# other.net
KiCad netlist of a schematic drawn in Altium Designer
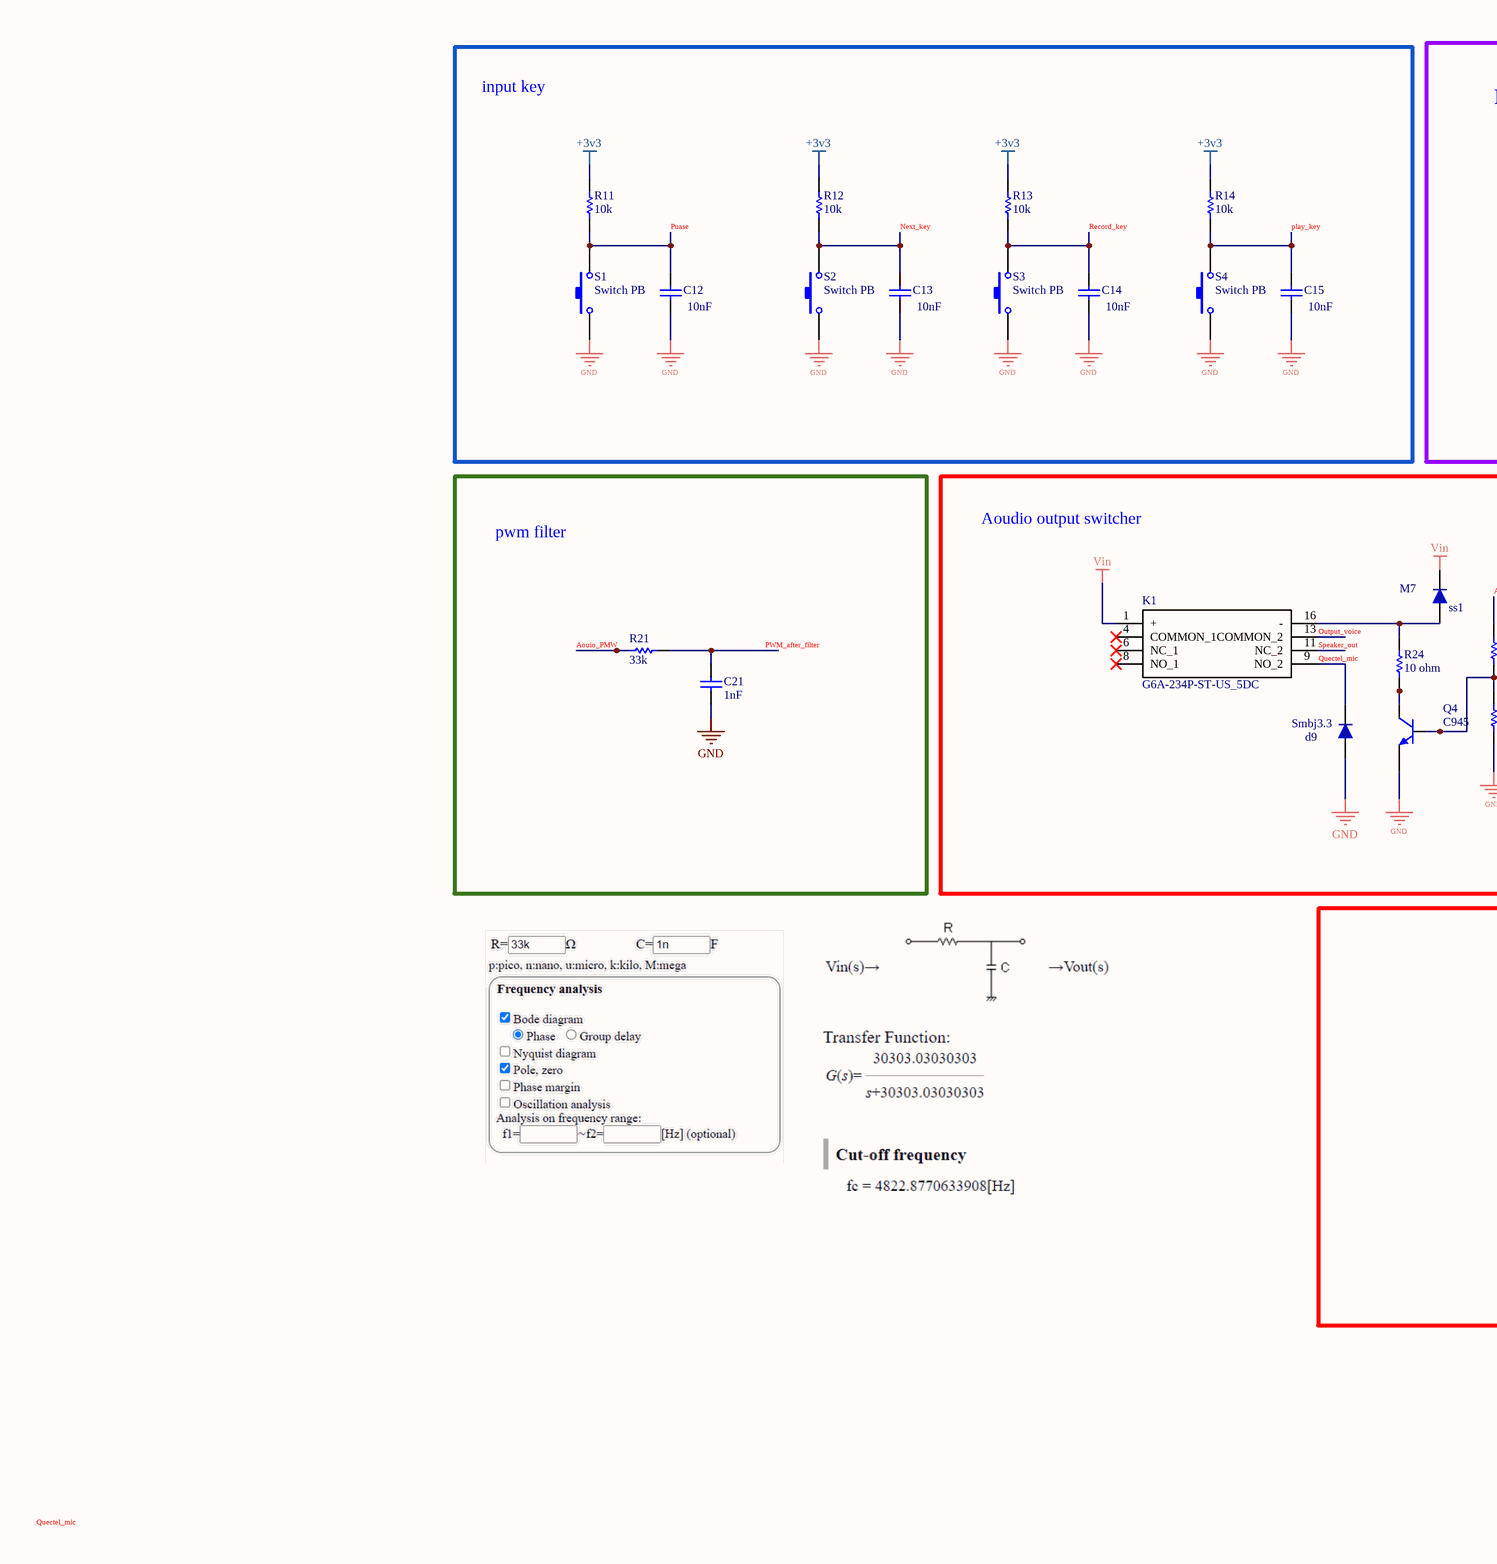
[diagram p0: other.SchDoc, left]
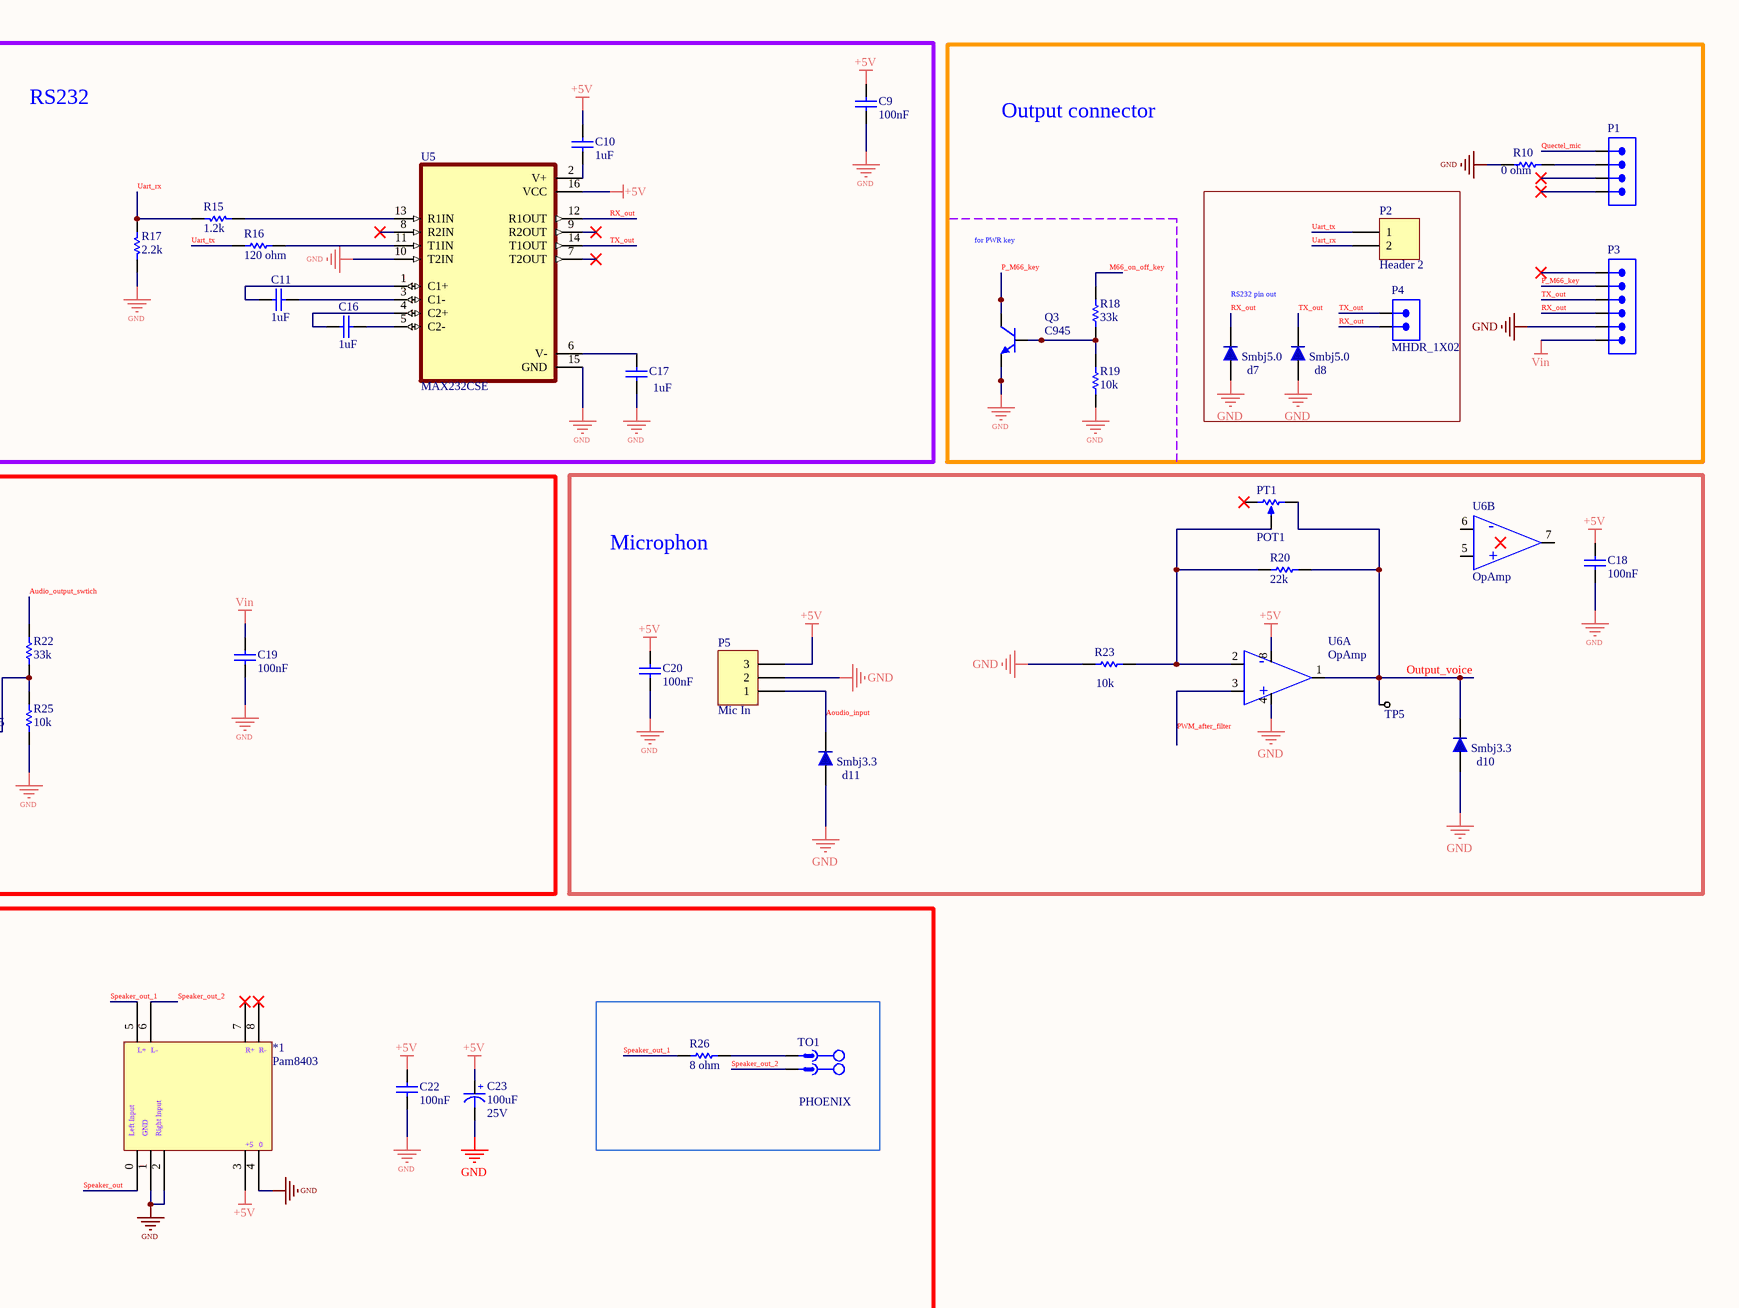
[diagram p1: other.SchDoc, right]

(export (version "E")
  (design (tool "Eeschema 10.0.6"))
  (components
    (comp (ref "*1") (value "Pam8403") (footprint "PAM8403") (libsource (lib "PAM8403") (part "Pam8403")))
    (comp (ref "C9")
      (value "100nF")
      (footprint "CAP805")
      (description "Capacitor")
      (fields (field (name "PUBLISHER") "Altium Limited"))
      (libsource (lib "componnect") (part "Cap"))
    )
    (comp (ref "C10")
      (value "1uF")
      (footprint "CAP805")
      (description "Capacitor")
      (fields (field (name "PUBLISHER") "Altium Limited"))
      (libsource (lib "componnect") (part "Cap"))
    )
    (comp (ref "C11")
      (value "1uF")
      (footprint "CAP805")
      (description "Capacitor")
      (fields (field (name "PUBLISHER") "Altium Limited"))
      (libsource (lib "componnect") (part "Cap"))
    )
    (comp (ref "C12")
      (value "10nF")
      (footprint "CAP805")
      (description "Capacitor")
      (fields (field (name "PUBLISHER") "Altium Limited"))
      (libsource (lib "componnect") (part "Cap"))
    )
    (comp (ref "C13")
      (value "10nF")
      (footprint "CAP805")
      (description "Capacitor")
      (fields (field (name "PUBLISHER") "Altium Limited"))
      (libsource (lib "componnect") (part "Cap"))
    )
    (comp (ref "C14")
      (value "10nF")
      (footprint "CAP805")
      (description "Capacitor")
      (fields (field (name "PUBLISHER") "Altium Limited"))
      (libsource (lib "componnect") (part "Cap"))
    )
    (comp (ref "C15")
      (value "10nF")
      (footprint "CAP805")
      (description "Capacitor")
      (fields (field (name "PUBLISHER") "Altium Limited"))
      (libsource (lib "componnect") (part "Cap"))
    )
    (comp (ref "C16")
      (value "1uF")
      (footprint "CAP805")
      (description "Capacitor")
      (fields (field (name "PUBLISHER") "Altium Limited"))
      (libsource (lib "componnect") (part "Cap"))
    )
    (comp (ref "C17")
      (value "1uF")
      (footprint "CAP805")
      (description "Capacitor")
      (fields (field (name "PUBLISHER") "Altium Limited"))
      (libsource (lib "componnect") (part "Cap"))
    )
    (comp (ref "C18")
      (value "100nF")
      (footprint "CAP805")
      (description "Capacitor")
      (fields (field (name "PUBLISHER") "Altium Limited"))
      (libsource (lib "componnect") (part "Cap"))
    )
    (comp (ref "C19")
      (value "100nF")
      (footprint "CAP805")
      (description "Capacitor")
      (fields (field (name "PUBLISHER") "Altium Limited"))
      (libsource (lib "componnect") (part "Cap"))
    )
    (comp (ref "C20")
      (value "100nF")
      (footprint "CAP805")
      (description "Capacitor")
      (fields (field (name "PUBLISHER") "Altium Limited"))
      (libsource (lib "componnect") (part "Cap"))
    )
    (comp (ref "C21")
      (value "1nF")
      (footprint "CAP805")
      (description "Capacitor")
      (fields (field (name "PUBLISHER") "Altium Limited"))
      (libsource (lib "componnect") (part "Cap"))
    )
    (comp (ref "C22")
      (value "100nF")
      (footprint "CAP805")
      (description "Capacitor")
      (fields (field (name "PUBLISHER") "Altium Limited"))
      (libsource (lib "componnect") (part "Cap"))
    )
    (comp (ref "C23")
      (value "100uF")
      (footprint "cap 03")
      (description "Polar Capacitor")
      (fields
        (field (name "VOLTAGE") "25V")
        (field (name "DESIGNER") "Eng. Saeid Jorablo")
        (field (name "PUBLISHER") "SJ Unlimited")
      )
      (libsource (lib "Schematic") (part "CAP_Polar"))
    )
    (comp (ref "d7")
      (value "Smbj5.0")
      (footprint "DIODE SMA (DO-214AC)")
      (fields (field (name "MANUFACTURER") "DC COMPONENTS") (field (name "DESIGNER") "Abbas Basereh"))
      (libsource (lib "componnect") (part "1n4007 SMD M7"))
    )
    (comp (ref "d8")
      (value "Smbj5.0")
      (footprint "DIODE SMA (DO-214AC)")
      (fields (field (name "MANUFACTURER") "DC COMPONENTS") (field (name "DESIGNER") "Abbas Basereh"))
      (libsource (lib "componnect") (part "1n4007 SMD M7"))
    )
    (comp (ref "d9")
      (value "Smbj3.3")
      (footprint "DIODE SMA (DO-214AC)")
      (description "Smbj5.0")
      (fields (field (name "MANUFACTURER") "DC COMPONENTS") (field (name "DESIGNER") "Abbas Basereh"))
      (libsource (lib "componnect") (part "1n4007 SMD M7"))
    )
    (comp (ref "d10")
      (value "Smbj3.3")
      (footprint "DIODE SMA (DO-214AC)")
      (description "Smbj5.0")
      (fields (field (name "MANUFACTURER") "DC COMPONENTS") (field (name "DESIGNER") "Abbas Basereh"))
      (libsource (lib "componnect") (part "1n4007 SMD M7"))
    )
    (comp (ref "d11")
      (value "Smbj3.3")
      (footprint "DIODE SMA (DO-214AC)")
      (description "Smbj5.0")
      (fields (field (name "MANUFACTURER") "DC COMPONENTS") (field (name "DESIGNER") "Abbas Basereh"))
      (libsource (lib "componnect") (part "1n4007 SMD M7"))
    )
    (comp (ref "K1")
      (value "G6A-234P-ST-US_5DC")
      (footprint "G6A234PSTUS5DC")
      (description "Relay or Contactor")
      (fields (field (name "MANUFACTURER_PART_NUMBER") "G6A-234P-ST-US 5DC"))
      (libsource (lib "*") (part "G6A-234P-ST-US_5DC"))
    )
    (comp (ref "P1")
      (value "xh 4pin")
      (footprint "XH 4 PIN-S")
      (libsource (lib "Connector_15 and Sockets") (part "MHDR_1X04"))
    )
    (comp (ref "P2")
      (value "Header 2")
      (footprint "HDR1X2")
      (description "Header, 2-Pin")
      (fields (field (name "PUBLISHER") "Altium Limited"))
      (libsource (lib "Schematic") (part "Header 2"))
    )
    (comp (ref "P3")
      (value "xh 6pin")
      (footprint "XH 6 PIN-S")
      (libsource (lib "Connector_15 and Sockets") (part "MHDR_1X06"))
    )
    (comp (ref "P4")
      (value "MHDR_1X02")
      (footprint "MHDR1X02-254P")
      (description "Male Header 1X02")
      (libsource (lib "Connector_15 and Sockets") (part "MHDR_1X02"))
    )
    (comp (ref "P5")
      (value "Mic In")
      (footprint "HDR1X3")
      (description "Header, 3-Pin")
      (fields (field (name "PUBLISHER") "Altium Limited"))
      (libsource (lib "Schematic") (part "Header 3"))
    )
    (comp (ref "PT1")
      (value "POT1")
      (footprint "POT1")
      (description "Variable Potentiometer standing")
      (fields (field (name "DESIGNER") "Seyed Mohsen Ghasemian"))
      (libsource (lib "usefully_Library") (part "POT1"))
    )
    (comp (ref "Q3")
      (value "C945")
      (footprint "C945")
      (description "NPN Transistor")
      (fields (field (name "DESIGNER") "Saeid Jorablo"))
      (libsource (lib "Schematic") (part "C945 2"))
    )
    (comp (ref "Q4")
      (value "C945")
      (footprint "C945")
      (description "NPN Transistor")
      (fields (field (name "DESIGNER") "Saeid Jorablo"))
      (libsource (lib "Schematic") (part "C945 2"))
    )
    (comp (ref "R10")
      (value "0 ohm")
      (footprint "RES0805")
      (description "RES 0805")
      (fields (field (name "DESIGNER") "Abbas Basereh"))
      (libsource (lib "Realy_Box_16_v6") (part "RES 0805 0.125W_5"))
    )
    (comp (ref "R11")
      (value "10k")
      (footprint "RES0805")
      (description "RES 0805")
      (fields (field (name "DESIGNER") "Abbas Basereh"))
      (libsource (lib "componnect") (part "RES 0805 0.125W_1"))
    )
    (comp (ref "R12")
      (value "10k")
      (footprint "RES0805")
      (description "RES 0805")
      (fields (field (name "DESIGNER") "Abbas Basereh"))
      (libsource (lib "componnect") (part "RES 0805 0.125W_1"))
    )
    (comp (ref "R13")
      (value "10k")
      (footprint "RES0805")
      (description "RES 0805")
      (fields (field (name "DESIGNER") "Abbas Basereh"))
      (libsource (lib "componnect") (part "RES 0805 0.125W_1"))
    )
    (comp (ref "R14")
      (value "10k")
      (footprint "RES0805")
      (description "RES 0805")
      (fields (field (name "DESIGNER") "Abbas Basereh"))
      (libsource (lib "componnect") (part "RES 0805 0.125W_1"))
    )
    (comp (ref "R15")
      (value "1.2k")
      (footprint "RES0805")
      (description "RES 0805")
      (fields (field (name "DESIGNER") "Abbas Basereh"))
      (libsource (lib "componnect") (part "RES 0805 0.125W_1"))
    )
    (comp (ref "R16")
      (value "120 ohm")
      (footprint "RES0805")
      (description "RES 0805")
      (fields (field (name "DESIGNER") "Abbas Basereh"))
      (libsource (lib "componnect") (part "RES 0805 0.125W_1"))
    )
    (comp (ref "R17")
      (value "2.2k")
      (footprint "RES0805")
      (description "RES 0805")
      (fields (field (name "DESIGNER") "Abbas Basereh"))
      (libsource (lib "componnect") (part "RES 0805 0.125W_1"))
    )
    (comp (ref "R18")
      (value "33k")
      (footprint "RES0805")
      (description "RES 0805")
      (fields (field (name "DESIGNER") "Abbas Basereh"))
      (libsource (lib "Realy_Box_16_v6") (part "RES 0805 0.125W_5"))
    )
    (comp (ref "R19")
      (value "10k")
      (footprint "RES0805")
      (description "RES 0805")
      (fields (field (name "DESIGNER") "Abbas Basereh"))
      (libsource (lib "Realy_Box_16_v6") (part "RES 0805 0.125W_5"))
    )
    (comp (ref "R20")
      (value "22k")
      (footprint "RES0805")
      (description "RES 0805")
      (fields (field (name "DESIGNER") "Abbas Basereh"))
      (libsource (lib "componnect") (part "RES 0805 0.125W_1"))
    )
    (comp (ref "R21")
      (value "33k")
      (footprint "RES0805")
      (description "RES 0805")
      (fields (field (name "DESIGNER") "Abbas Basereh"))
      (libsource (lib "componnect") (part "RES 0805 0.125W_1"))
    )
    (comp (ref "R22")
      (value "33k")
      (footprint "RES0805")
      (description "RES 0805")
      (fields (field (name "DESIGNER") "Abbas Basereh"))
      (libsource (lib "Realy_Box_16_v6") (part "RES 0805 0.125W_5"))
    )
    (comp (ref "R23")
      (value "10k")
      (footprint "RES0805")
      (description "RES 0805")
      (fields (field (name "DESIGNER") "Abbas Basereh"))
      (libsource (lib "componnect") (part "RES 0805 0.125W_1"))
    )
    (comp (ref "R24")
      (value "10 ohm")
      (footprint "RES0805")
      (description "RES 0805")
      (fields (field (name "DESIGNER") "Abbas Basereh"))
      (libsource (lib "Realy_Box_16_v6") (part "RES 0805 0.125W_5"))
    )
    (comp (ref "R25")
      (value "10k")
      (footprint "RES0805")
      (description "RES 0805")
      (fields (field (name "DESIGNER") "Abbas Basereh"))
      (libsource (lib "Realy_Box_16_v6") (part "RES 0805 0.125W_5"))
    )
    (comp (ref "R26")
      (value "8 ohm")
      (footprint "RES0805")
      (description "RES 0805")
      (fields (field (name "DESIGNER") "Abbas Basereh"))
      (libsource (lib "Realy_Box_16_v6") (part "RES 0805 0.125W_5"))
    )
    (comp (ref "S1")
      (value "Switch PB")
      (footprint "Switch - Push to On")
      (description "Push Button Switch")
      (libsource (lib "My_Library") (part "Switch PB"))
    )
    (comp (ref "S2")
      (value "Switch PB")
      (footprint "Switch - Push to On")
      (description "Push Button Switch")
      (libsource (lib "My_Library") (part "Switch PB"))
    )
    (comp (ref "S3")
      (value "Switch PB")
      (footprint "Switch - Push to On")
      (description "Push Button Switch")
      (libsource (lib "My_Library") (part "Switch PB"))
    )
    (comp (ref "S4")
      (value "Switch PB")
      (footprint "Switch - Push to On")
      (description "Push Button Switch")
      (libsource (lib "My_Library") (part "Switch PB"))
    )
    (comp (ref "ss1")
      (value "M7")
      (footprint "DIODE SMA (DO-214AC)")
      (description "Standard Rectifiers")
      (fields (field (name "MANUFACTURER") "DC COMPONENTS") (field (name "DESIGNER") "Abbas Basereh"))
      (libsource (lib "Realy_Box_16_v6") (part "1n4007 SMD M7"))
    )
    (comp (ref "TO1")
      (value "PHOENIX")
      (footprint "CON_MSTBA02")
      (description "2 Pitch: 5.08 mm Color: green Contact surface: Tin Assembly")
      (fields
        (field (name "MANUFACTURER") "PHOENIX CONTACT")
        (field (name "VOLTAGE") "320 V")
        (field (name "DESIGNER") "ABBAS BASEREH")
      )
      (libsource (lib "Realy_Box_16_v6") (part "CON_Phoenix_MSTB_02"))
    )
    (comp (ref "TP5")
      (value "~")
      (footprint "TP10")
      (description "Test Point")
      (fields (field (name "DESIGNER") "Eng. Saeid Jorablo"))
      (libsource (lib "General_06 Passive Components") (part "Test Point"))
    )
    (comp (ref "U5")
      (value "MAX232CSE")
      (footprint "SOIC127P600X175-16N")
      (fields (field (name "MF") "{'manufacturer': u'Analog Devices'}"))
      (libsource (lib "SnapEDA_Library") (part "MAX232CSE"))
    )
    (comp (ref "U6")
      (value "OpAmp")
      (footprint "DIP8")
      (description "Dual Low Noise Operational Amplifier (OpAmp)")
      (libsource (lib "My_Library") (part "OpAmp"))
    )
  )
  (nets
    (net (code "1") (name "+3v3") (class "Default")
      (node (ref "R11") (pin "2") (pinfunction "2_2") (pintype "passive"))
      (node (ref "R12") (pin "2") (pinfunction "2_2") (pintype "passive"))
      (node (ref "R13") (pin "2") (pinfunction "2_2") (pintype "passive"))
      (node (ref "R14") (pin "2") (pinfunction "2_2") (pintype "passive"))
    )
    (net (code "2") (name "+5V") (class "Default")
      (node (ref "*1") (pin "3") (pinfunction "3_3") (pintype "passive"))
      (node (ref "C10") (pin "1") (pinfunction "1_1") (pintype "passive"))
      (node (ref "C18") (pin "1") (pinfunction "1_1") (pintype "passive"))
      (node (ref "C20") (pin "1") (pinfunction "1_1") (pintype "passive"))
      (node (ref "C22") (pin "1") (pinfunction "1_1") (pintype "passive"))
      (node (ref "C23") (pin "1") (pinfunction "+_1") (pintype "passive"))
      (node (ref "C9") (pin "1") (pinfunction "1_1") (pintype "passive"))
      (node (ref "P5") (pin "3") (pinfunction "3_3") (pintype "passive"))
      (node (ref "U5") (pin "16") (pinfunction "VCC_16") (pintype "power_in"))
      (node (ref "U6") (pin "8") (pinfunction "V+_8") (pintype "passive"))
    )
    (net (code "3") (name "/Aoudio_input") (class "Default")
      (node (ref "P5") (pin "1") (pinfunction "1_1") (pintype "passive"))
      (node (ref "d11") (pin "2") (pintype "passive"))
    )
    (net (code "4") (name "/Aouio_PMW") (class "Default")
      (node (ref "R21") (pin "2") (pinfunction "2_2") (pintype "passive"))
    )
    (net (code "5") (name "/Audio_output_swtich") (class "Default")
      (node (ref "R22") (pin "1") (pinfunction "1_1") (pintype "passive"))
    )
    (net (code "6") (name "/M66_on_off_key") (class "Default")
      (node (ref "R18") (pin "1") (pinfunction "1_1") (pintype "passive"))
    )
    (net (code "7") (name "/Next_key") (class "Default")
      (node (ref "C13") (pin "2") (pinfunction "2_2") (pintype "passive"))
      (node (ref "R12") (pin "1") (pinfunction "1_1") (pintype "passive"))
      (node (ref "S2") (pin "2") (pinfunction "2_2") (pintype "passive"))
    )
    (net (code "8") (name "/Output_voice") (class "Default")
      (node (ref "K1") (pin "13") (pinfunction "COMMON_2_13") (pintype "passive"))
      (node (ref "PT1") (pin "2") (pinfunction "BOT_2") (pintype "passive"))
      (node (ref "R20") (pin "1") (pinfunction "1_1") (pintype "passive"))
      (node (ref "TP5") (pin "1") (pinfunction "TP_1") (pintype "passive"))
      (node (ref "U6") (pin "1") (pinfunction "Output_1") (pintype "passive"))
      (node (ref "d10") (pin "2") (pintype "passive"))
    )
    (net (code "9") (name "/PWM_after_filter") (class "Default")
      (node (ref "C21") (pin "1") (pinfunction "1_1") (pintype "passive"))
      (node (ref "R21") (pin "1") (pinfunction "1_1") (pintype "passive"))
      (node (ref "U6") (pin "3") (pinfunction "Noninverter_Input_3") (pintype "passive"))
    )
    (net (code "10") (name "/P_M66_key") (class "Default")
      (node (ref "P3") (pin "2") (pinfunction "2_2") (pintype "passive"))
      (node (ref "Q3") (pin "2") (pinfunction "C_2") (pintype "passive"))
    )
    (net (code "11") (name "/Puase") (class "Default")
      (node (ref "C12") (pin "2") (pinfunction "2_2") (pintype "passive"))
      (node (ref "R11") (pin "1") (pinfunction "1_1") (pintype "passive"))
      (node (ref "S1") (pin "2") (pinfunction "2_2") (pintype "passive"))
    )
    (net (code "12") (name "/Quectel_mic") (class "Default")
      (node (ref "K1") (pin "9") (pinfunction "NO_2_9") (pintype "passive"))
      (node (ref "P1") (pin "1") (pinfunction "1_1") (pintype "passive"))
      (node (ref "d9") (pin "2") (pintype "passive"))
    )
    (net (code "13") (name "/RX_out") (class "Default")
      (node (ref "P3") (pin "4") (pinfunction "4_4") (pintype "passive"))
      (node (ref "P4") (pin "2") (pinfunction "2_2") (pintype "passive"))
      (node (ref "U5") (pin "12") (pinfunction "R1OUT_12") (pintype "output"))
      (node (ref "d7") (pin "2") (pintype "passive"))
    )
    (net (code "14") (name "/Record_key") (class "Default")
      (node (ref "C14") (pin "2") (pinfunction "2_2") (pintype "passive"))
      (node (ref "R13") (pin "1") (pinfunction "1_1") (pintype "passive"))
      (node (ref "S3") (pin "2") (pinfunction "2_2") (pintype "passive"))
    )
    (net (code "15") (name "/Speaker_out") (class "Default")
      (node (ref "*1") (pin "0") (pinfunction "0_0") (pintype "passive"))
      (node (ref "K1") (pin "11") (pinfunction "NC_2_11") (pintype "passive"))
    )
    (net (code "16") (name "/Speaker_out_1") (class "Default")
      (node (ref "*1") (pin "5") (pinfunction "5_5") (pintype "passive"))
      (node (ref "R26") (pin "1") (pinfunction "1_1") (pintype "passive"))
    )
    (net (code "17") (name "/Speaker_out_2") (class "Default")
      (node (ref "*1") (pin "6") (pinfunction "6_6") (pintype "passive"))
      (node (ref "TO1") (pin "2") (pinfunction "2_2") (pintype "passive"))
    )
    (net (code "18") (name "/TX_out") (class "Default")
      (node (ref "P3") (pin "3") (pinfunction "3_3") (pintype "passive"))
      (node (ref "P4") (pin "1") (pinfunction "1_1") (pintype "passive"))
      (node (ref "U5") (pin "14") (pinfunction "T1OUT_14") (pintype "output"))
      (node (ref "d8") (pin "2") (pintype "passive"))
    )
    (net (code "19") (name "/Uart_rx") (class "Default")
      (node (ref "P2") (pin "2") (pinfunction "2_2") (pintype "passive"))
      (node (ref "R15") (pin "1") (pinfunction "1_1") (pintype "passive"))
      (node (ref "R17") (pin "2") (pinfunction "2_2") (pintype "passive"))
    )
    (net (code "20") (name "/Uart_tx") (class "Default")
      (node (ref "P2") (pin "1") (pinfunction "1_1") (pintype "passive"))
      (node (ref "R16") (pin "2") (pinfunction "2_2") (pintype "passive"))
    )
    (net (code "21") (name "/play_key") (class "Default")
      (node (ref "C15") (pin "2") (pinfunction "2_2") (pintype "passive"))
      (node (ref "R14") (pin "1") (pinfunction "1_1") (pintype "passive"))
      (node (ref "S4") (pin "2") (pinfunction "2_2") (pintype "passive"))
    )
    (net (code "22") (name "GND") (class "Default")
      (node (ref "*1") (pin "1") (pinfunction "1_1") (pintype "passive"))
      (node (ref "*1") (pin "2") (pinfunction "2_2") (pintype "passive"))
      (node (ref "*1") (pin "4") (pinfunction "4_4") (pintype "passive"))
      (node (ref "C12") (pin "1") (pinfunction "1_1") (pintype "passive"))
      (node (ref "C13") (pin "1") (pinfunction "1_1") (pintype "passive"))
      (node (ref "C14") (pin "1") (pinfunction "1_1") (pintype "passive"))
      (node (ref "C15") (pin "1") (pinfunction "1_1") (pintype "passive"))
      (node (ref "C17") (pin "1") (pinfunction "1_1") (pintype "passive"))
      (node (ref "C18") (pin "2") (pinfunction "2_2") (pintype "passive"))
      (node (ref "C19") (pin "2") (pinfunction "2_2") (pintype "passive"))
      (node (ref "C20") (pin "2") (pinfunction "2_2") (pintype "passive"))
      (node (ref "C21") (pin "2") (pinfunction "2_2") (pintype "passive"))
      (node (ref "C22") (pin "2") (pinfunction "2_2") (pintype "passive"))
      (node (ref "C23") (pin "2") (pinfunction "-_2") (pintype "passive"))
      (node (ref "C9") (pin "2") (pinfunction "2_2") (pintype "passive"))
      (node (ref "P3") (pin "5") (pinfunction "5_5") (pintype "passive"))
      (node (ref "P5") (pin "2") (pinfunction "2_2") (pintype "passive"))
      (node (ref "Q3") (pin "1") (pinfunction "E_1") (pintype "passive"))
      (node (ref "Q4") (pin "1") (pinfunction "E_1") (pintype "passive"))
      (node (ref "R10") (pin "2") (pinfunction "2_2") (pintype "passive"))
      (node (ref "R17") (pin "1") (pinfunction "1_1") (pintype "passive"))
      (node (ref "R19") (pin "2") (pinfunction "2_2") (pintype "passive"))
      (node (ref "R23") (pin "2") (pinfunction "2_2") (pintype "passive"))
      (node (ref "R25") (pin "2") (pinfunction "2_2") (pintype "passive"))
      (node (ref "S1") (pin "1") (pinfunction "1_1") (pintype "passive"))
      (node (ref "S2") (pin "1") (pinfunction "1_1") (pintype "passive"))
      (node (ref "S3") (pin "1") (pinfunction "1_1") (pintype "passive"))
      (node (ref "S4") (pin "1") (pinfunction "1_1") (pintype "passive"))
      (node (ref "U5") (pin "10") (pinfunction "T2IN_10") (pintype "input"))
      (node (ref "U5") (pin "15") (pinfunction "GND_15") (pintype "power_in"))
      (node (ref "U6") (pin "4") (pinfunction "V-_4") (pintype "passive"))
      (node (ref "d10") (pin "1") (pintype "passive"))
      (node (ref "d11") (pin "1") (pintype "passive"))
      (node (ref "d7") (pin "1") (pintype "passive"))
      (node (ref "d8") (pin "1") (pintype "passive"))
      (node (ref "d9") (pin "1") (pintype "passive"))
    )
    (net (code "23") (name "Net-(K1--)") (class "Default")
      (node (ref "K1") (pin "16") (pinfunction "-_16") (pintype "passive"))
      (node (ref "R24") (pin "1") (pinfunction "1_1") (pintype "passive"))
      (node (ref "ss1") (pin "1") (pintype "passive"))
    )
    (net (code "24") (name "Net-(P1-Pad2)") (class "Default")
      (node (ref "P1") (pin "2") (pinfunction "2_2") (pintype "passive"))
      (node (ref "R10") (pin "1") (pinfunction "1_1") (pintype "passive"))
    )
    (net (code "25") (name "Net-(PT1-TAP)") (class "Default")
      (node (ref "PT1") (pin "3") (pinfunction "TAP_3") (pintype "passive"))
      (node (ref "R20") (pin "2") (pinfunction "2_2") (pintype "passive"))
      (node (ref "R23") (pin "1") (pinfunction "1_1") (pintype "passive"))
      (node (ref "U6") (pin "2") (pinfunction "Inverter_Input_2") (pintype "passive"))
    )
    (net (code "26") (name "Net-(Q3-B)") (class "Default")
      (node (ref "Q3") (pin "3") (pinfunction "B_3") (pintype "passive"))
      (node (ref "R18") (pin "2") (pinfunction "2_2") (pintype "passive"))
      (node (ref "R19") (pin "1") (pinfunction "1_1") (pintype "passive"))
    )
    (net (code "27") (name "Net-(Q4-B)") (class "Default")
      (node (ref "Q4") (pin "3") (pinfunction "B_3") (pintype "passive"))
      (node (ref "R22") (pin "2") (pinfunction "2_2") (pintype "passive"))
      (node (ref "R25") (pin "1") (pinfunction "1_1") (pintype "passive"))
    )
    (net (code "28") (name "Net-(Q4-C)") (class "Default")
      (node (ref "Q4") (pin "2") (pinfunction "C_2") (pintype "passive"))
      (node (ref "R24") (pin "2") (pinfunction "2_2") (pintype "passive"))
    )
    (net (code "29") (name "Net-(R26-Pad2)") (class "Default")
      (node (ref "R26") (pin "2") (pinfunction "2_2") (pintype "passive"))
      (node (ref "TO1") (pin "1") (pinfunction "1_1") (pintype "passive"))
    )
    (net (code "30") (name "Net-(U5-C1+)") (class "Default")
      (node (ref "C11") (pin "2") (pinfunction "2_2") (pintype "passive"))
      (node (ref "U5") (pin "1") (pinfunction "C1+_1") (pintype "bidirectional"))
    )
    (net (code "31") (name "Net-(U5-C1-)") (class "Default")
      (node (ref "C11") (pin "1") (pinfunction "1_1") (pintype "passive"))
      (node (ref "U5") (pin "3") (pinfunction "C1-_3") (pintype "bidirectional"))
    )
    (net (code "32") (name "Net-(U5-C2+)") (class "Default")
      (node (ref "C16") (pin "2") (pinfunction "2_2") (pintype "passive"))
      (node (ref "U5") (pin "4") (pinfunction "C2+_4") (pintype "bidirectional"))
    )
    (net (code "33") (name "Net-(U5-C2-)") (class "Default")
      (node (ref "C16") (pin "1") (pinfunction "1_1") (pintype "passive"))
      (node (ref "U5") (pin "5") (pinfunction "C2-_5") (pintype "bidirectional"))
    )
    (net (code "34") (name "Net-(U5-R1IN)") (class "Default")
      (node (ref "R15") (pin "2") (pinfunction "2_2") (pintype "passive"))
      (node (ref "U5") (pin "13") (pinfunction "R1IN_13") (pintype "input"))
    )
    (net (code "35") (name "Net-(U5-T1IN)") (class "Default")
      (node (ref "R16") (pin "1") (pinfunction "1_1") (pintype "passive"))
      (node (ref "U5") (pin "11") (pinfunction "T1IN_11") (pintype "input"))
    )
    (net (code "36") (name "Net-(U5-V+)") (class "Default")
      (node (ref "C10") (pin "2") (pinfunction "2_2") (pintype "passive"))
      (node (ref "U5") (pin "2") (pinfunction "V+_2") (pintype "power_in"))
    )
    (net (code "37") (name "Net-(U5-V-)") (class "Default")
      (node (ref "C17") (pin "2") (pinfunction "2_2") (pintype "passive"))
      (node (ref "U5") (pin "6") (pinfunction "V-_6") (pintype "power_in"))
    )
    (net (code "38") (name "Vin") (class "Default")
      (node (ref "C19") (pin "1") (pinfunction "1_1") (pintype "passive"))
      (node (ref "K1") (pin "1") (pinfunction "+_1") (pintype "passive"))
      (node (ref "P3") (pin "6") (pinfunction "6_6") (pintype "passive"))
      (node (ref "ss1") (pin "2") (pintype "passive"))
    )
    (net (code "39") (name "unconnected-(*1-Pad7)") (class "Default")
      (node (ref "*1") (pin "7") (pinfunction "7_7") (pintype "passive+no_connect"))
    )
    (net (code "40") (name "unconnected-(*1-Pad8)") (class "Default")
      (node (ref "*1") (pin "8") (pinfunction "8_8") (pintype "passive+no_connect"))
    )
    (net (code "41") (name "unconnected-(K1-COMMON_1-Pad4)") (class "Default")
      (node (ref "K1") (pin "4") (pinfunction "COMMON_1_4") (pintype "passive+no_connect"))
    )
    (net (code "42") (name "unconnected-(K1-NC_1-Pad6)") (class "Default")
      (node (ref "K1") (pin "6") (pinfunction "NC_1_6") (pintype "passive+no_connect"))
    )
    (net (code "43") (name "unconnected-(K1-NO_1-Pad8)") (class "Default")
      (node (ref "K1") (pin "8") (pinfunction "NO_1_8") (pintype "passive+no_connect"))
    )
    (net (code "44") (name "unconnected-(P1-Pad3)") (class "Default")
      (node (ref "P1") (pin "3") (pinfunction "3_3") (pintype "passive+no_connect"))
    )
    (net (code "45") (name "unconnected-(P1-Pad4)") (class "Default")
      (node (ref "P1") (pin "4") (pinfunction "4_4") (pintype "passive+no_connect"))
    )
    (net (code "46") (name "unconnected-(P3-Pad1)") (class "Default")
      (node (ref "P3") (pin "1") (pinfunction "1_1") (pintype "passive+no_connect"))
    )
    (net (code "47") (name "unconnected-(PT1-TOP-Pad1)") (class "Default")
      (node (ref "PT1") (pin "1") (pinfunction "TOP_1") (pintype "passive+no_connect"))
    )
    (net (code "48") (name "unconnected-(U5-R2IN-Pad8)") (class "Default")
      (node (ref "U5") (pin "8") (pinfunction "R2IN_8") (pintype "input+no_connect"))
    )
    (net (code "49") (name "unconnected-(U5-R2OUT-Pad9)") (class "Default")
      (node (ref "U5") (pin "9") (pinfunction "R2OUT_9") (pintype "output+no_connect"))
    )
    (net (code "50") (name "unconnected-(U5-T2OUT-Pad7)") (class "Default")
      (node (ref "U5") (pin "7") (pinfunction "T2OUT_7") (pintype "output+no_connect"))
    )
    (net (code "51") (name "unconnected-(U6B-Inverter_Input-Pad6)") (class "Default")
      (node (ref "U6") (pin "6") (pinfunction "Inverter_Input_6") (pintype "passive"))
    )
    (net (code "52") (name "unconnected-(U6B-Noninverter_Input-Pad5)") (class "Default")
      (node (ref "U6") (pin "5") (pinfunction "Noninverter_Input_5") (pintype "passive"))
    )
    (net (code "53") (name "unconnected-(U6B-Output-Pad7)") (class "Default")
      (node (ref "U6") (pin "7") (pinfunction "Output_7") (pintype "passive"))
    )
  )
)
